# GPIO.net
KiCad netlist of a schematic drawn in Altium Designer
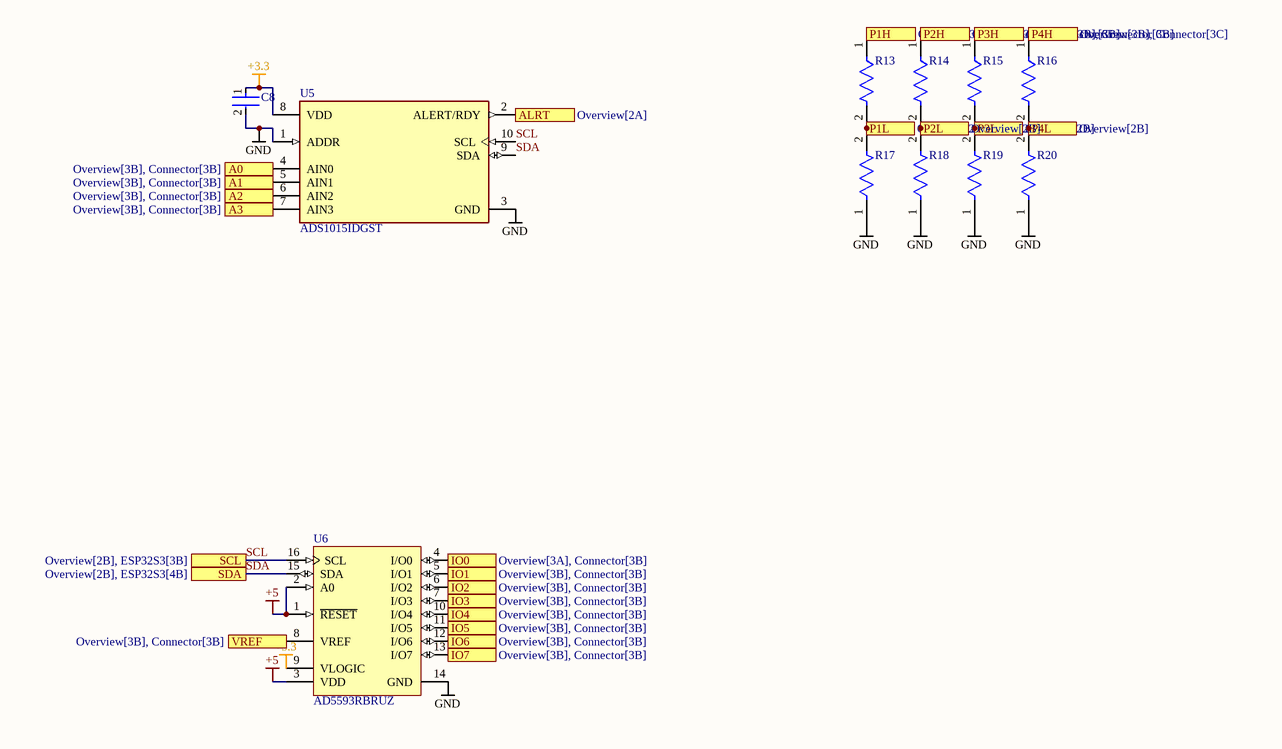
[diagram p0: GPIO.SchDoc]

(export (version "E")
  (design (tool "Eeschema 10.0.6"))
  (components
    (comp (ref "C8")
      (value "GRM033R60J104KE19D")
      (footprint "FP-GRM033-0_03-MFG")
      (description "Chip Multilayer Ceramic Capacitors for General Purpose, 0201, 0.10uF, X5R, 15%, 10%, 6.3V")
      (fields (field (name "VOLTAGE") "6.3V") (field (name "TOLERANCE") "10%"))
      (libsource (lib "Altium Content Vault") (part "b4654b650e69147ec39a6b967a45e02"))
    )
    (comp (ref "R13")
      (value "CR1206-JW-752ELF")
      (footprint "FP-CR1206-IPC_B")
      (description "Thick Film Chip Resistors 1206 7.5kΩ 0.25W 5% 200ppm/°C")
      (fields (field (name "TOLERANCE") "5%"))
      (libsource (lib "Altium Content Vault") (part "1029c3af85768c4190bb7ad29bc67b5"))
    )
    (comp (ref "R14")
      (value "CR1206-JW-752ELF")
      (footprint "FP-CR1206-IPC_B")
      (description "Thick Film Chip Resistors 1206 7.5kΩ 0.25W 5% 200ppm/°C")
      (fields (field (name "TOLERANCE") "5%"))
      (libsource (lib "Altium Content Vault") (part "1029c3af85768c4190bb7ad29bc67b5"))
    )
    (comp (ref "R15")
      (value "CR1206-JW-752ELF")
      (footprint "FP-CR1206-IPC_B")
      (description "Thick Film Chip Resistors 1206 7.5kΩ 0.25W 5% 200ppm/°C")
      (fields (field (name "TOLERANCE") "5%"))
      (libsource (lib "Altium Content Vault") (part "1029c3af85768c4190bb7ad29bc67b5"))
    )
    (comp (ref "R16")
      (value "CR1206-JW-752ELF")
      (footprint "FP-CR1206-IPC_B")
      (description "Thick Film Chip Resistors 1206 7.5kΩ 0.25W 5% 200ppm/°C")
      (fields (field (name "TOLERANCE") "5%"))
      (libsource (lib "Altium Content Vault") (part "1029c3af85768c4190bb7ad29bc67b5"))
    )
    (comp (ref "R17")
      (value "CRCW04022K70FKED")
      (footprint "FP-CRCW0402-e3-IPC_A")
      (description "RES Thick Film, 2.7kΩ, 1%, 0.063W, 100ppm/°C, 0402")
      (fields (field (name "TOLERANCE") "1%"))
      (libsource (lib "Altium Content Vault") (part "1029c3af85768c4190bb7ad29bc67b5"))
    )
    (comp (ref "R18")
      (value "CRCW04022K70FKED")
      (footprint "FP-CRCW0402-e3-IPC_A")
      (description "RES Thick Film, 2.7kΩ, 1%, 0.063W, 100ppm/°C, 0402")
      (fields (field (name "TOLERANCE") "1%"))
      (libsource (lib "Altium Content Vault") (part "1029c3af85768c4190bb7ad29bc67b5"))
    )
    (comp (ref "R19")
      (value "CRCW04022K70FKED")
      (footprint "FP-CRCW0402-e3-IPC_A")
      (description "RES Thick Film, 2.7kΩ, 1%, 0.063W, 100ppm/°C, 0402")
      (fields (field (name "TOLERANCE") "1%"))
      (libsource (lib "Altium Content Vault") (part "1029c3af85768c4190bb7ad29bc67b5"))
    )
    (comp (ref "R20")
      (value "CRCW04022K70FKED")
      (footprint "FP-CRCW0402-e3-IPC_A")
      (description "RES Thick Film, 2.7kΩ, 1%, 0.063W, 100ppm/°C, 0402")
      (fields (field (name "TOLERANCE") "1%"))
      (libsource (lib "Altium Content Vault") (part "1029c3af85768c4190bb7ad29bc67b5"))
    )
    (comp (ref "U5")
      (value "ADS1015IDGST")
      (footprint "FP-DGS0010A-MFG")
      (description "IC ADC 12BIT SIGMA-DELTA 10VSSOP")
      (libsource (lib "Altium Content Vault") (part "0fb225032f4bd54fd540a872e776a50"))
    )
    (comp (ref "U6")
      (value "AD5593RBRUZ")
      (footprint "ADI-RU-16_L")
      (fields (field (name "MANUFACTURER") "AnalogDevicesInc."))
      (libsource (lib "Altium Content Vault") (part "ADI-AD5593R-RU-16"))
    )
  )
  (nets
    (net (code "1") (name "+3.3") (class "Default")
      (node (ref "C8") (pin "1") (pinfunction "1_1") (pintype "passive"))
      (node (ref "U5") (pin "8") (pinfunction "VDD_8") (pintype "power_in"))
      (node (ref "U6") (pin "9") (pinfunction "VLOGIC_9") (pintype "power_in"))
    )
    (net (code "2") (name "+5") (class "Default")
      (node (ref "U6") (pin "1") (pinfunction "~{RESET}_1") (pintype "input"))
      (node (ref "U6") (pin "2") (pinfunction "A0_2") (pintype "input"))
      (node (ref "U6") (pin "3") (pinfunction "VDD_3") (pintype "power_in"))
    )
    (net (code "3") (name "/A0") (class "Default")
      (node (ref "U5") (pin "4") (pinfunction "AIN0_4") (pintype "passive"))
    )
    (net (code "4") (name "/A1") (class "Default")
      (node (ref "U5") (pin "5") (pinfunction "AIN1_5") (pintype "passive"))
    )
    (net (code "5") (name "/A2") (class "Default")
      (node (ref "U5") (pin "6") (pinfunction "AIN2_6") (pintype "passive"))
    )
    (net (code "6") (name "/A3") (class "Default")
      (node (ref "U5") (pin "7") (pinfunction "AIN3_7") (pintype "passive"))
    )
    (net (code "7") (name "/ALRT") (class "Default")
      (node (ref "U5") (pin "2") (pinfunction "ALERT/RDY_2") (pintype "output"))
    )
    (net (code "8") (name "/IO0") (class "Default")
      (node (ref "U6") (pin "4") (pinfunction "I/O0_4") (pintype "bidirectional"))
    )
    (net (code "9") (name "/IO1") (class "Default")
      (node (ref "U6") (pin "5") (pinfunction "I/O1_5") (pintype "bidirectional"))
    )
    (net (code "10") (name "/IO2") (class "Default")
      (node (ref "U6") (pin "6") (pinfunction "I/O2_6") (pintype "bidirectional"))
    )
    (net (code "11") (name "/IO3") (class "Default")
      (node (ref "U6") (pin "7") (pinfunction "I/O3_7") (pintype "bidirectional"))
    )
    (net (code "12") (name "/IO4") (class "Default")
      (node (ref "U6") (pin "10") (pinfunction "I/O4_10") (pintype "bidirectional"))
    )
    (net (code "13") (name "/IO5") (class "Default")
      (node (ref "U6") (pin "11") (pinfunction "I/O5_11") (pintype "bidirectional"))
    )
    (net (code "14") (name "/IO6") (class "Default")
      (node (ref "U6") (pin "12") (pinfunction "I/O6_12") (pintype "bidirectional"))
    )
    (net (code "15") (name "/IO7") (class "Default")
      (node (ref "U6") (pin "13") (pinfunction "I/O7_13") (pintype "bidirectional"))
    )
    (net (code "16") (name "/P1H") (class "Default")
      (node (ref "R13") (pin "1") (pinfunction "1_1") (pintype "passive"))
    )
    (net (code "17") (name "/P1L") (class "Default")
      (node (ref "R13") (pin "2") (pinfunction "2_2") (pintype "passive"))
      (node (ref "R17") (pin "2") (pinfunction "2_2") (pintype "passive"))
    )
    (net (code "18") (name "/P2H") (class "Default")
      (node (ref "R14") (pin "1") (pinfunction "1_1") (pintype "passive"))
    )
    (net (code "19") (name "/P2L") (class "Default")
      (node (ref "R14") (pin "2") (pinfunction "2_2") (pintype "passive"))
      (node (ref "R18") (pin "2") (pinfunction "2_2") (pintype "passive"))
    )
    (net (code "20") (name "/P3H") (class "Default")
      (node (ref "R15") (pin "1") (pinfunction "1_1") (pintype "passive"))
    )
    (net (code "21") (name "/P3L") (class "Default")
      (node (ref "R15") (pin "2") (pinfunction "2_2") (pintype "passive"))
      (node (ref "R19") (pin "2") (pinfunction "2_2") (pintype "passive"))
    )
    (net (code "22") (name "/P4H") (class "Default")
      (node (ref "R16") (pin "1") (pinfunction "1_1") (pintype "passive"))
    )
    (net (code "23") (name "/P4L") (class "Default")
      (node (ref "R16") (pin "2") (pinfunction "2_2") (pintype "passive"))
      (node (ref "R20") (pin "2") (pinfunction "2_2") (pintype "passive"))
    )
    (net (code "24") (name "/SCL") (class "Default")
      (node (ref "U5") (pin "10") (pinfunction "SCL_10") (pintype "input"))
      (node (ref "U6") (pin "16") (pinfunction "SCL_16") (pintype "input"))
    )
    (net (code "25") (name "/SDA") (class "Default")
      (node (ref "U5") (pin "9") (pinfunction "SDA_9") (pintype "bidirectional"))
      (node (ref "U6") (pin "15") (pinfunction "SDA_15") (pintype "bidirectional"))
    )
    (net (code "26") (name "/VREF") (class "Default")
      (node (ref "U6") (pin "8") (pinfunction "VREF_8") (pintype "passive"))
    )
    (net (code "27") (name "GND") (class "Default")
      (node (ref "C8") (pin "2") (pinfunction "2_2") (pintype "passive"))
      (node (ref "R17") (pin "1") (pinfunction "1_1") (pintype "passive"))
      (node (ref "R18") (pin "1") (pinfunction "1_1") (pintype "passive"))
      (node (ref "R19") (pin "1") (pinfunction "1_1") (pintype "passive"))
      (node (ref "R20") (pin "1") (pinfunction "1_1") (pintype "passive"))
      (node (ref "U5") (pin "1") (pinfunction "ADDR_1") (pintype "input"))
      (node (ref "U5") (pin "3") (pinfunction "GND_3") (pintype "power_in"))
      (node (ref "U6") (pin "14") (pinfunction "GND_14") (pintype "power_in"))
    )
  )
)
